# Diff2SE.net
KiCad netlist of a schematic drawn in Altium Designer
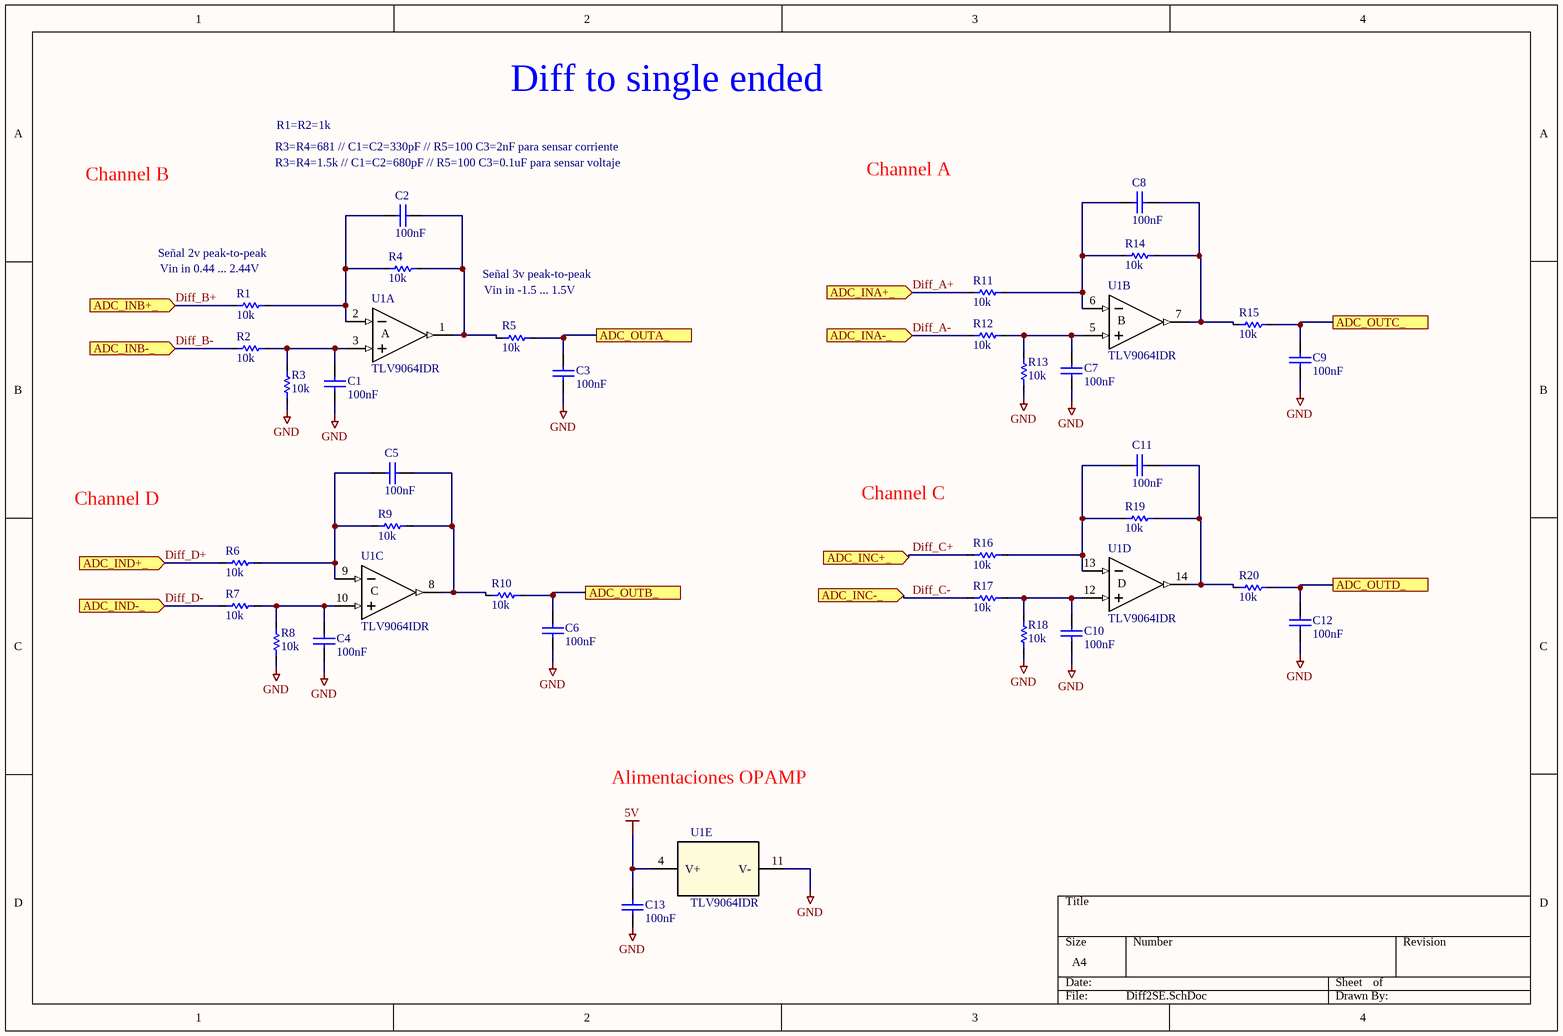
[diagram p0: Diff2SE.SchDoc]

(export (version "E")
  (design (tool "Eeschema 10.0.6"))
  (components
    (comp (ref "C1")
      (value "100nF")
      (footprint "CAP_0603")
      (description "0.1µF ±10% 50V Ceramic Capacitor X7R 0603 (1608 Metric)")
      (fields (field (name "MF") "KEMET") (field (name "CREATED") "2020_06_15_DAarancibia"))
      (libsource (lib "Schlib1") (part "Cap_0603"))
    )
    (comp (ref "C2")
      (value "100nF")
      (footprint "CAP_0603")
      (description "0.1µF ±10% 50V Ceramic Capacitor X7R 0603 (1608 Metric)")
      (fields (field (name "MF") "KEMET") (field (name "CREATED") "2020_06_15_DAarancibia"))
      (libsource (lib "Schlib1") (part "Cap_0603"))
    )
    (comp (ref "C3")
      (value "100nF")
      (footprint "CAP_0603")
      (description "0.1µF ±10% 50V Ceramic Capacitor X7R 0603 (1608 Metric)")
      (fields (field (name "MF") "KEMET") (field (name "CREATED") "2020_06_15_DAarancibia"))
      (libsource (lib "Schlib1") (part "Cap_0603"))
    )
    (comp (ref "C4")
      (value "100nF")
      (footprint "CAP_0603")
      (description "0.1µF ±10% 50V Ceramic Capacitor X7R 0603 (1608 Metric)")
      (fields (field (name "MF") "KEMET") (field (name "CREATED") "2020_06_15_DAarancibia"))
      (libsource (lib "Schlib1") (part "Cap_0603"))
    )
    (comp (ref "C5")
      (value "100nF")
      (footprint "CAP_0603")
      (description "0.1µF ±10% 50V Ceramic Capacitor X7R 0603 (1608 Metric)")
      (fields (field (name "MF") "KEMET") (field (name "CREATED") "2020_06_15_DAarancibia"))
      (libsource (lib "Schlib1") (part "Cap_0603"))
    )
    (comp (ref "C6")
      (value "100nF")
      (footprint "CAP_0603")
      (description "0.1µF ±10% 50V Ceramic Capacitor X7R 0603 (1608 Metric)")
      (fields (field (name "MF") "KEMET") (field (name "CREATED") "2020_06_15_DAarancibia"))
      (libsource (lib "Schlib1") (part "Cap_0603"))
    )
    (comp (ref "C7")
      (value "100nF")
      (footprint "CAP_0603")
      (description "0.1µF ±10% 50V Ceramic Capacitor X7R 0603 (1608 Metric)")
      (fields (field (name "MF") "KEMET") (field (name "CREATED") "2020_06_15_DAarancibia"))
      (libsource (lib "Schlib1") (part "Cap_0603"))
    )
    (comp (ref "C8")
      (value "100nF")
      (footprint "CAP_0603")
      (description "0.1µF ±10% 50V Ceramic Capacitor X7R 0603 (1608 Metric)")
      (fields (field (name "MF") "KEMET") (field (name "CREATED") "2020_06_15_DAarancibia"))
      (libsource (lib "Schlib1") (part "Cap_0603"))
    )
    (comp (ref "C9")
      (value "100nF")
      (footprint "CAP_0603")
      (description "0.1µF ±10% 50V Ceramic Capacitor X7R 0603 (1608 Metric)")
      (fields (field (name "MF") "KEMET") (field (name "CREATED") "2020_06_15_DAarancibia"))
      (libsource (lib "Schlib1") (part "Cap_0603"))
    )
    (comp (ref "C10")
      (value "100nF")
      (footprint "CAP_0603")
      (description "0.1µF ±10% 50V Ceramic Capacitor X7R 0603 (1608 Metric)")
      (fields (field (name "MF") "KEMET") (field (name "CREATED") "2020_06_15_DAarancibia"))
      (libsource (lib "Schlib1") (part "Cap_0603"))
    )
    (comp (ref "C11")
      (value "100nF")
      (footprint "CAP_0603")
      (description "0.1µF ±10% 50V Ceramic Capacitor X7R 0603 (1608 Metric)")
      (fields (field (name "MF") "KEMET") (field (name "CREATED") "2020_06_15_DAarancibia"))
      (libsource (lib "Schlib1") (part "Cap_0603"))
    )
    (comp (ref "C12")
      (value "100nF")
      (footprint "CAP_0603")
      (description "0.1µF ±10% 50V Ceramic Capacitor X7R 0603 (1608 Metric)")
      (fields (field (name "MF") "KEMET") (field (name "CREATED") "2020_06_15_DAarancibia"))
      (libsource (lib "Schlib1") (part "Cap_0603"))
    )
    (comp (ref "C13")
      (value "100nF")
      (footprint "CAP_0603")
      (description "0.1µF ±10% 50V Ceramic Capacitor X7R 0603 (1608 Metric)")
      (fields (field (name "MF") "KEMET") (field (name "CREATED") "2020_06_15_DAarancibia"))
      (libsource (lib "Schlib1") (part "Cap_0603"))
    )
    (comp (ref "R1")
      (value "10k")
      (footprint "RES_0603")
      (fields
        (field (name "MF") "Panasonic Electronic Components")
        (field (name "CREATED") "2020_06_15_DAarancibia")
      )
      (libsource (lib "Schlib1") (part "Res_0603"))
    )
    (comp (ref "R2")
      (value "10k")
      (footprint "RES_0603")
      (fields
        (field (name "MF") "Panasonic Electronic Components")
        (field (name "CREATED") "2020_06_15_DAarancibia")
      )
      (libsource (lib "Schlib1") (part "Res_0603"))
    )
    (comp (ref "R3")
      (value "10k")
      (footprint "RES_0603")
      (fields
        (field (name "MF") "Panasonic Electronic Components")
        (field (name "CREATED") "2020_06_15_DAarancibia")
      )
      (libsource (lib "Schlib1") (part "Res_0603"))
    )
    (comp (ref "R4")
      (value "10k")
      (footprint "RES_0603")
      (fields
        (field (name "MF") "Panasonic Electronic Components")
        (field (name "CREATED") "2020_06_15_DAarancibia")
      )
      (libsource (lib "Schlib1") (part "Res_0603"))
    )
    (comp (ref "R5")
      (value "10k")
      (footprint "RES_0603")
      (fields
        (field (name "MF") "Panasonic Electronic Components")
        (field (name "CREATED") "2020_06_15_DAarancibia")
      )
      (libsource (lib "Schlib1") (part "Res_0603"))
    )
    (comp (ref "R6")
      (value "10k")
      (footprint "RES_0603")
      (fields
        (field (name "MF") "Panasonic Electronic Components")
        (field (name "CREATED") "2020_06_15_DAarancibia")
      )
      (libsource (lib "Schlib1") (part "Res_0603"))
    )
    (comp (ref "R7")
      (value "10k")
      (footprint "RES_0603")
      (fields
        (field (name "MF") "Panasonic Electronic Components")
        (field (name "CREATED") "2020_06_15_DAarancibia")
      )
      (libsource (lib "Schlib1") (part "Res_0603"))
    )
    (comp (ref "R8")
      (value "10k")
      (footprint "RES_0603")
      (fields
        (field (name "MF") "Panasonic Electronic Components")
        (field (name "CREATED") "2020_06_15_DAarancibia")
      )
      (libsource (lib "Schlib1") (part "Res_0603"))
    )
    (comp (ref "R9")
      (value "10k")
      (footprint "RES_0603")
      (fields
        (field (name "MF") "Panasonic Electronic Components")
        (field (name "CREATED") "2020_06_15_DAarancibia")
      )
      (libsource (lib "Schlib1") (part "Res_0603"))
    )
    (comp (ref "R10")
      (value "10k")
      (footprint "RES_0603")
      (fields
        (field (name "MF") "Panasonic Electronic Components")
        (field (name "CREATED") "2020_06_15_DAarancibia")
      )
      (libsource (lib "Schlib1") (part "Res_0603"))
    )
    (comp (ref "R11")
      (value "10k")
      (footprint "RES_0603")
      (fields
        (field (name "MF") "Panasonic Electronic Components")
        (field (name "CREATED") "2020_06_15_DAarancibia")
      )
      (libsource (lib "Schlib1") (part "Res_0603"))
    )
    (comp (ref "R12")
      (value "10k")
      (footprint "RES_0603")
      (fields
        (field (name "MF") "Panasonic Electronic Components")
        (field (name "CREATED") "2020_06_15_DAarancibia")
      )
      (libsource (lib "Schlib1") (part "Res_0603"))
    )
    (comp (ref "R13")
      (value "10k")
      (footprint "RES_0603")
      (fields
        (field (name "MF") "Panasonic Electronic Components")
        (field (name "CREATED") "2020_06_15_DAarancibia")
      )
      (libsource (lib "Schlib1") (part "Res_0603"))
    )
    (comp (ref "R14")
      (value "10k")
      (footprint "RES_0603")
      (fields
        (field (name "MF") "Panasonic Electronic Components")
        (field (name "CREATED") "2020_06_15_DAarancibia")
      )
      (libsource (lib "Schlib1") (part "Res_0603"))
    )
    (comp (ref "R15")
      (value "10k")
      (footprint "RES_0603")
      (fields
        (field (name "MF") "Panasonic Electronic Components")
        (field (name "CREATED") "2020_06_15_DAarancibia")
      )
      (libsource (lib "Schlib1") (part "Res_0603"))
    )
    (comp (ref "R16")
      (value "10k")
      (footprint "RES_0603")
      (fields
        (field (name "MF") "Panasonic Electronic Components")
        (field (name "CREATED") "2020_06_15_DAarancibia")
      )
      (libsource (lib "Schlib1") (part "Res_0603"))
    )
    (comp (ref "R17")
      (value "10k")
      (footprint "RES_0603")
      (fields
        (field (name "MF") "Panasonic Electronic Components")
        (field (name "CREATED") "2020_06_15_DAarancibia")
      )
      (libsource (lib "Schlib1") (part "Res_0603"))
    )
    (comp (ref "R18")
      (value "10k")
      (footprint "RES_0603")
      (fields
        (field (name "MF") "Panasonic Electronic Components")
        (field (name "CREATED") "2020_06_15_DAarancibia")
      )
      (libsource (lib "Schlib1") (part "Res_0603"))
    )
    (comp (ref "R19")
      (value "10k")
      (footprint "RES_0603")
      (fields
        (field (name "MF") "Panasonic Electronic Components")
        (field (name "CREATED") "2020_06_15_DAarancibia")
      )
      (libsource (lib "Schlib1") (part "Res_0603"))
    )
    (comp (ref "R20")
      (value "10k")
      (footprint "RES_0603")
      (fields
        (field (name "MF") "Panasonic Electronic Components")
        (field (name "CREATED") "2020_06_15_DAarancibia")
      )
      (libsource (lib "Schlib1") (part "Res_0603"))
    )
    (comp (ref "U1")
      (value "TLV9064IDR")
      (footprint "D0014A_N")
      (description "No Description Available")
      (libsource (lib "Schlib1") (part "TLV9064IDR"))
    )
  )
  (nets
    (net (code "1") (name "/ADC_OUTA_") (class "Default")
      (node (ref "C3") (pin "1") (pinfunction "1_1") (pintype "passive"))
      (node (ref "R5") (pin "2") (pinfunction "2_2") (pintype "passive"))
    )
    (net (code "2") (name "/ADC_OUTB_") (class "Default")
      (node (ref "C6") (pin "1") (pinfunction "1_1") (pintype "passive"))
      (node (ref "R10") (pin "2") (pinfunction "2_2") (pintype "passive"))
    )
    (net (code "3") (name "/ADC_OUTC_") (class "Default")
      (node (ref "C9") (pin "1") (pinfunction "1_1") (pintype "passive"))
      (node (ref "R15") (pin "2") (pinfunction "2_2") (pintype "passive"))
    )
    (net (code "4") (name "/ADC_OUTD_") (class "Default")
      (node (ref "C12") (pin "1") (pinfunction "1_1") (pintype "passive"))
      (node (ref "R20") (pin "2") (pinfunction "2_2") (pintype "passive"))
    )
    (net (code "5") (name "/Diff_A+") (class "Default")
      (node (ref "R11") (pin "1") (pinfunction "1_1") (pintype "passive"))
    )
    (net (code "6") (name "/Diff_A-") (class "Default")
      (node (ref "R12") (pin "1") (pinfunction "1_1") (pintype "passive"))
    )
    (net (code "7") (name "/Diff_B+") (class "Default")
      (node (ref "R1") (pin "1") (pinfunction "1_1") (pintype "passive"))
    )
    (net (code "8") (name "/Diff_B-") (class "Default")
      (node (ref "R2") (pin "1") (pinfunction "1_1") (pintype "passive"))
    )
    (net (code "9") (name "/Diff_C+") (class "Default")
      (node (ref "R16") (pin "1") (pinfunction "1_1") (pintype "passive"))
    )
    (net (code "10") (name "/Diff_C-") (class "Default")
      (node (ref "R17") (pin "1") (pinfunction "1_1") (pintype "passive"))
    )
    (net (code "11") (name "/Diff_D+") (class "Default")
      (node (ref "R6") (pin "1") (pinfunction "1_1") (pintype "passive"))
    )
    (net (code "12") (name "/Diff_D-") (class "Default")
      (node (ref "R7") (pin "1") (pinfunction "1_1") (pintype "passive"))
    )
    (net (code "13") (name "5V") (class "Default")
      (node (ref "C13") (pin "1") (pinfunction "1_1") (pintype "passive"))
      (node (ref "U1") (pin "4") (pinfunction "V+_4") (pintype "power_in"))
    )
    (net (code "14") (name "GND") (class "Default")
      (node (ref "C1") (pin "2") (pinfunction "2_2") (pintype "passive"))
      (node (ref "C10") (pin "2") (pinfunction "2_2") (pintype "passive"))
      (node (ref "C12") (pin "2") (pinfunction "2_2") (pintype "passive"))
      (node (ref "C13") (pin "2") (pinfunction "2_2") (pintype "passive"))
      (node (ref "C3") (pin "2") (pinfunction "2_2") (pintype "passive"))
      (node (ref "C4") (pin "2") (pinfunction "2_2") (pintype "passive"))
      (node (ref "C6") (pin "2") (pinfunction "2_2") (pintype "passive"))
      (node (ref "C7") (pin "2") (pinfunction "2_2") (pintype "passive"))
      (node (ref "C9") (pin "2") (pinfunction "2_2") (pintype "passive"))
      (node (ref "R13") (pin "2") (pinfunction "2_2") (pintype "passive"))
      (node (ref "R18") (pin "2") (pinfunction "2_2") (pintype "passive"))
      (node (ref "R3") (pin "2") (pinfunction "2_2") (pintype "passive"))
      (node (ref "R8") (pin "2") (pinfunction "2_2") (pintype "passive"))
      (node (ref "U1") (pin "11") (pinfunction "V-_11") (pintype "power_in"))
    )
    (net (code "15") (name "Net-(U1A-IN+)") (class "Default")
      (node (ref "C1") (pin "1") (pinfunction "1_1") (pintype "passive"))
      (node (ref "R2") (pin "2") (pinfunction "2_2") (pintype "passive"))
      (node (ref "R3") (pin "1") (pinfunction "1_1") (pintype "passive"))
      (node (ref "U1") (pin "3") (pinfunction "IN+_3") (pintype "input"))
    )
    (net (code "16") (name "Net-(U1A-IN-)") (class "Default")
      (node (ref "C2") (pin "1") (pinfunction "1_1") (pintype "passive"))
      (node (ref "R1") (pin "2") (pinfunction "2_2") (pintype "passive"))
      (node (ref "R4") (pin "1") (pinfunction "1_1") (pintype "passive"))
      (node (ref "U1") (pin "2") (pinfunction "IN-_2") (pintype "input"))
    )
    (net (code "17") (name "Net-(U1A-OUT)") (class "Default")
      (node (ref "C2") (pin "2") (pinfunction "2_2") (pintype "passive"))
      (node (ref "R4") (pin "2") (pinfunction "2_2") (pintype "passive"))
      (node (ref "R5") (pin "1") (pinfunction "1_1") (pintype "passive"))
      (node (ref "U1") (pin "1") (pinfunction "OUT_1") (pintype "output"))
    )
    (net (code "18") (name "Net-(U1B-IN+)") (class "Default")
      (node (ref "C7") (pin "1") (pinfunction "1_1") (pintype "passive"))
      (node (ref "R12") (pin "2") (pinfunction "2_2") (pintype "passive"))
      (node (ref "R13") (pin "1") (pinfunction "1_1") (pintype "passive"))
      (node (ref "U1") (pin "5") (pinfunction "IN+_5") (pintype "input"))
    )
    (net (code "19") (name "Net-(U1B-IN-)") (class "Default")
      (node (ref "C8") (pin "1") (pinfunction "1_1") (pintype "passive"))
      (node (ref "R11") (pin "2") (pinfunction "2_2") (pintype "passive"))
      (node (ref "R14") (pin "1") (pinfunction "1_1") (pintype "passive"))
      (node (ref "U1") (pin "6") (pinfunction "IN-_6") (pintype "input"))
    )
    (net (code "20") (name "Net-(U1B-OUT)") (class "Default")
      (node (ref "C8") (pin "2") (pinfunction "2_2") (pintype "passive"))
      (node (ref "R14") (pin "2") (pinfunction "2_2") (pintype "passive"))
      (node (ref "R15") (pin "1") (pinfunction "1_1") (pintype "passive"))
      (node (ref "U1") (pin "7") (pinfunction "OUT_7") (pintype "output"))
    )
    (net (code "21") (name "Net-(U1C-IN+)") (class "Default")
      (node (ref "C4") (pin "1") (pinfunction "1_1") (pintype "passive"))
      (node (ref "R7") (pin "2") (pinfunction "2_2") (pintype "passive"))
      (node (ref "R8") (pin "1") (pinfunction "1_1") (pintype "passive"))
      (node (ref "U1") (pin "10") (pinfunction "IN+_10") (pintype "input"))
    )
    (net (code "22") (name "Net-(U1C-IN-)") (class "Default")
      (node (ref "C5") (pin "1") (pinfunction "1_1") (pintype "passive"))
      (node (ref "R6") (pin "2") (pinfunction "2_2") (pintype "passive"))
      (node (ref "R9") (pin "1") (pinfunction "1_1") (pintype "passive"))
      (node (ref "U1") (pin "9") (pinfunction "IN-_9") (pintype "input"))
    )
    (net (code "23") (name "Net-(U1C-OUT)") (class "Default")
      (node (ref "C5") (pin "2") (pinfunction "2_2") (pintype "passive"))
      (node (ref "R10") (pin "1") (pinfunction "1_1") (pintype "passive"))
      (node (ref "R9") (pin "2") (pinfunction "2_2") (pintype "passive"))
      (node (ref "U1") (pin "8") (pinfunction "OUT_8") (pintype "output"))
    )
    (net (code "24") (name "Net-(U1D-IN+)") (class "Default")
      (node (ref "C10") (pin "1") (pinfunction "1_1") (pintype "passive"))
      (node (ref "R17") (pin "2") (pinfunction "2_2") (pintype "passive"))
      (node (ref "R18") (pin "1") (pinfunction "1_1") (pintype "passive"))
      (node (ref "U1") (pin "12") (pinfunction "IN+_12") (pintype "input"))
    )
    (net (code "25") (name "Net-(U1D-IN-)") (class "Default")
      (node (ref "C11") (pin "1") (pinfunction "1_1") (pintype "passive"))
      (node (ref "R16") (pin "2") (pinfunction "2_2") (pintype "passive"))
      (node (ref "R19") (pin "1") (pinfunction "1_1") (pintype "passive"))
      (node (ref "U1") (pin "13") (pinfunction "IN-_13") (pintype "input"))
    )
    (net (code "26") (name "Net-(U1D-OUT)") (class "Default")
      (node (ref "C11") (pin "2") (pinfunction "2_2") (pintype "passive"))
      (node (ref "R19") (pin "2") (pinfunction "2_2") (pintype "passive"))
      (node (ref "R20") (pin "1") (pinfunction "1_1") (pintype "passive"))
      (node (ref "U1") (pin "14") (pinfunction "OUT_14") (pintype "output"))
    )
  )
)
